# CAN.net
KiCad netlist of a schematic drawn in Altium Designer
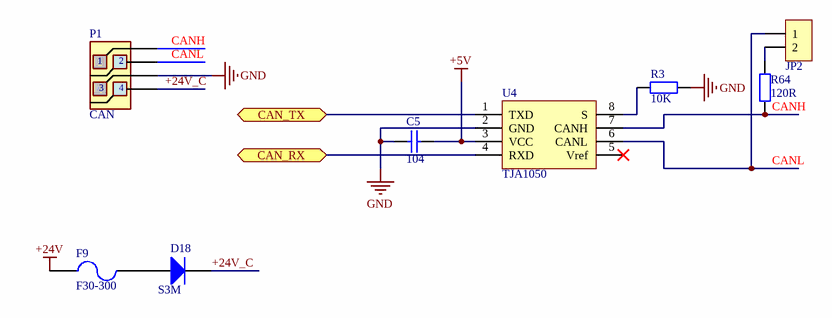
[diagram p0: CAN.SchDoc]

(export (version "E")
  (design (tool "Eeschema 10.0.6"))
  (components
    (comp (ref "C5")
      (value "104")
      (footprint "C 0805")
      (description "Capacitor")
      (fields (field (name "PUBLISHER") "Altium Limited"))
      (libsource (lib "Miscellaneous Devices") (part "Cap"))
    )
    (comp (ref "D18") (value "S3M") (footprint "SMC") (libsource (lib "YXF_ComponentLibrary") (part "Diode")))
    (comp (ref "F9")
      (value "F30-300")
      (footprint "FU 1812")
      (description "Fuse")
      (fields (field (name "PUBLISHER") "Altium Limited"))
      (libsource (lib "YXF_ComponentLibrary") (part "Fuse 2"))
    )
    (comp (ref "JP2")
      (value "HDR-1X2")
      (footprint "HDR-1X2")
      (description "2P接插件")
      (fields (field (name "版权归属") "源创客"))
      (libsource (lib "接插件") (part "Header 2"))
    )
    (comp (ref "P1") (value "CAN") (footprint "557-2x2") (libsource (lib "*") (part "CON4L")))
    (comp (ref "R3") (value "10K") (footprint "R 0805") (libsource (lib "any") (part "Res1")))
    (comp (ref "R64") (value "120R") (footprint "R 0805") (libsource (lib "") (part "Res1_1")))
    (comp (ref "U4")
      (value "TJA1050")
      (footprint "SO8")
      (description "CAN")
      (libsource (lib "YS_STM32f103") (part "SN65HVD230"))
    )
  )
  (nets
    (net (code "1") (name "+5V") (class "Default")
      (node (ref "C5") (pin "2") (pinfunction "2_2") (pintype "passive"))
      (node (ref "U4") (pin "3") (pinfunction "VCC_3") (pintype "passive"))
    )
    (net (code "2") (name "+24V") (class "Default")
      (node (ref "F9") (pin "1") (pinfunction "1_1") (pintype "passive"))
    )
    (net (code "3") (name "/+24V_C") (class "Default")
      (node (ref "D18") (pin "2") (pinfunction "2_2") (pintype "passive"))
      (node (ref "P1") (pin "4") (pinfunction "4_4") (pintype "passive"))
    )
    (net (code "4") (name "/CANH") (class "Default")
      (node (ref "P1") (pin "1") (pinfunction "1_1") (pintype "passive"))
      (node (ref "R64") (pin "2") (pinfunction "2_2") (pintype "passive"))
      (node (ref "U4") (pin "7") (pinfunction "CANH_7") (pintype "passive"))
    )
    (net (code "5") (name "/CANL") (class "Default")
      (node (ref "JP2") (pin "1") (pinfunction "1_1") (pintype "passive"))
      (node (ref "P1") (pin "2") (pinfunction "2_2") (pintype "passive"))
      (node (ref "U4") (pin "6") (pinfunction "CANL_6") (pintype "passive"))
    )
    (net (code "6") (name "/CAN_RX") (class "Default")
      (node (ref "U4") (pin "4") (pinfunction "RXD_4") (pintype "passive"))
    )
    (net (code "7") (name "/CAN_TX") (class "Default")
      (node (ref "U4") (pin "1") (pinfunction "TXD_1") (pintype "passive"))
    )
    (net (code "8") (name "GND") (class "Default")
      (node (ref "C5") (pin "1") (pinfunction "1_1") (pintype "passive"))
      (node (ref "P1") (pin "3") (pinfunction "3_3") (pintype "passive"))
      (node (ref "R3") (pin "2") (pinfunction "2_2") (pintype "passive"))
      (node (ref "U4") (pin "2") (pinfunction "GND_2") (pintype "passive"))
    )
    (net (code "9") (name "Net-(D18-Pad1)") (class "Default")
      (node (ref "D18") (pin "1") (pinfunction "1_1") (pintype "passive"))
      (node (ref "F9") (pin "2") (pinfunction "2_2") (pintype "passive"))
    )
    (net (code "10") (name "Net-(JP2-Pad2)") (class "Default")
      (node (ref "JP2") (pin "2") (pinfunction "2_2") (pintype "passive"))
      (node (ref "R64") (pin "1") (pinfunction "1_1") (pintype "passive"))
    )
    (net (code "11") (name "Net-(U4-S)") (class "Default")
      (node (ref "R3") (pin "1") (pinfunction "1_1") (pintype "passive"))
      (node (ref "U4") (pin "8") (pinfunction "S_8") (pintype "passive"))
    )
    (net (code "12") (name "unconnected-(U4-Vref-Pad5)") (class "Default")
      (node (ref "U4") (pin "5") (pinfunction "Vref_5") (pintype "passive+no_connect"))
    )
  )
)
